# QFN-20_4x4mm_Breakout.net
KiCad netlist of a schematic drawn in EAGLE
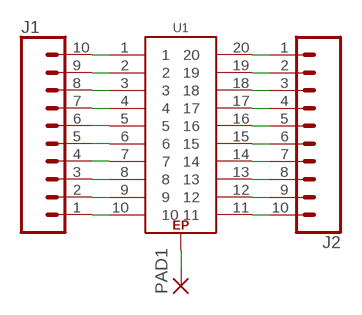
[diagram p0: schematic, sheet 1]

(export (version "E")
  (design (tool "Eeschema 10.0.6"))
  (components
    (comp (ref "J1")
      (value "CONN_10\"")
      (footprint "eagle-import:1X10")
      (libsource (lib "eagle-import") (part "CONN_10{dblquote}"))
    )
    (comp (ref "J2")
      (value "CONN_10\"")
      (footprint "eagle-import:1X10")
      (libsource (lib "eagle-import") (part "CONN_10{dblquote}"))
    )
    (comp (ref "PAD1")
      (value "SMD2")
      (footprint "eagle-import:SMD1,27-2,54")
      (fields (field (name "MPN") "DNP"))
      (libsource (lib "eagle-import") (part "SMD2"))
    )
    (comp (ref "U1")
      (value "GEN_20_EPQFN-20_4X4")
      (footprint "eagle-import:QFN20")
      (libsource (lib "eagle-import") (part "GEN_20_EPQFN-20_4X4"))
    )
  )
  (nets
    (net (code "1") (name "Net-(J1-Pad1)") (class "Default")
      (node (ref "J1") (pin "1") (pinfunction "1_1") (pintype "passive"))
      (node (ref "U1") (pin "10") (pinfunction "10_10") (pintype "bidirectional"))
    )
    (net (code "2") (name "Net-(J1-Pad2)") (class "Default")
      (node (ref "J1") (pin "2") (pinfunction "2_2") (pintype "passive"))
      (node (ref "U1") (pin "9") (pinfunction "9_9") (pintype "bidirectional"))
    )
    (net (code "3") (name "Net-(J1-Pad3)") (class "Default")
      (node (ref "J1") (pin "3") (pinfunction "3_3") (pintype "passive"))
      (node (ref "U1") (pin "8") (pinfunction "8_8") (pintype "bidirectional"))
    )
    (net (code "4") (name "Net-(J1-Pad4)") (class "Default")
      (node (ref "J1") (pin "4") (pinfunction "4_4") (pintype "passive"))
      (node (ref "U1") (pin "7") (pinfunction "7_7") (pintype "bidirectional"))
    )
    (net (code "5") (name "Net-(J1-Pad5)") (class "Default")
      (node (ref "J1") (pin "5") (pinfunction "5_5") (pintype "passive"))
      (node (ref "U1") (pin "6") (pinfunction "6_6") (pintype "bidirectional"))
    )
    (net (code "6") (name "Net-(J1-Pad6)") (class "Default")
      (node (ref "J1") (pin "6") (pinfunction "6_6") (pintype "passive"))
      (node (ref "U1") (pin "5") (pinfunction "5_5") (pintype "bidirectional"))
    )
    (net (code "7") (name "Net-(J1-Pad7)") (class "Default")
      (node (ref "J1") (pin "7") (pinfunction "7_7") (pintype "passive"))
      (node (ref "U1") (pin "4") (pinfunction "4_4") (pintype "bidirectional"))
    )
    (net (code "8") (name "Net-(J1-Pad8)") (class "Default")
      (node (ref "J1") (pin "8") (pinfunction "8_8") (pintype "passive"))
      (node (ref "U1") (pin "3") (pinfunction "3_3") (pintype "bidirectional"))
    )
    (net (code "9") (name "Net-(J1-Pad9)") (class "Default")
      (node (ref "J1") (pin "9") (pinfunction "9_9") (pintype "passive"))
      (node (ref "U1") (pin "2") (pinfunction "2_2") (pintype "bidirectional"))
    )
    (net (code "10") (name "Net-(J1-Pad10)") (class "Default")
      (node (ref "J1") (pin "10") (pinfunction "10_10") (pintype "passive"))
      (node (ref "U1") (pin "1") (pinfunction "1_1") (pintype "bidirectional"))
    )
    (net (code "11") (name "Net-(J2-Pad1)") (class "Default")
      (node (ref "J2") (pin "1") (pinfunction "1_1") (pintype "passive"))
      (node (ref "U1") (pin "20") (pinfunction "20_20") (pintype "bidirectional"))
    )
    (net (code "12") (name "Net-(J2-Pad2)") (class "Default")
      (node (ref "J2") (pin "2") (pinfunction "2_2") (pintype "passive"))
      (node (ref "U1") (pin "19") (pinfunction "19_19") (pintype "bidirectional"))
    )
    (net (code "13") (name "Net-(J2-Pad3)") (class "Default")
      (node (ref "J2") (pin "3") (pinfunction "3_3") (pintype "passive"))
      (node (ref "U1") (pin "18") (pinfunction "18_18") (pintype "bidirectional"))
    )
    (net (code "14") (name "Net-(J2-Pad4)") (class "Default")
      (node (ref "J2") (pin "4") (pinfunction "4_4") (pintype "passive"))
      (node (ref "U1") (pin "17") (pinfunction "17_17") (pintype "bidirectional"))
    )
    (net (code "15") (name "Net-(J2-Pad5)") (class "Default")
      (node (ref "J2") (pin "5") (pinfunction "5_5") (pintype "passive"))
      (node (ref "U1") (pin "16") (pinfunction "16_16") (pintype "bidirectional"))
    )
    (net (code "16") (name "Net-(J2-Pad6)") (class "Default")
      (node (ref "J2") (pin "6") (pinfunction "6_6") (pintype "passive"))
      (node (ref "U1") (pin "15") (pinfunction "15_15") (pintype "bidirectional"))
    )
    (net (code "17") (name "Net-(J2-Pad7)") (class "Default")
      (node (ref "J2") (pin "7") (pinfunction "7_7") (pintype "passive"))
      (node (ref "U1") (pin "14") (pinfunction "14_14") (pintype "bidirectional"))
    )
    (net (code "18") (name "Net-(J2-Pad8)") (class "Default")
      (node (ref "J2") (pin "8") (pinfunction "8_8") (pintype "passive"))
      (node (ref "U1") (pin "13") (pinfunction "13_13") (pintype "bidirectional"))
    )
    (net (code "19") (name "Net-(J2-Pad9)") (class "Default")
      (node (ref "J2") (pin "9") (pinfunction "9_9") (pintype "passive"))
      (node (ref "U1") (pin "12") (pinfunction "12_12") (pintype "bidirectional"))
    )
    (net (code "20") (name "Net-(J2-Pad10)") (class "Default")
      (node (ref "J2") (pin "10") (pinfunction "10_10") (pintype "passive"))
      (node (ref "U1") (pin "11") (pinfunction "11_11") (pintype "bidirectional"))
    )
    (net (code "21") (name "Net-(PAD1-P)") (class "Default")
      (node (ref "PAD1") (pin "1") (pinfunction "P_1") (pintype "passive"))
      (node (ref "U1") (pin "EP") (pinfunction "EP_EP") (pintype "passive"))
    )
  )
)
